# Mainboard_Geneva_Interface.net
KiCad netlist of a schematic drawn in Altium Designer
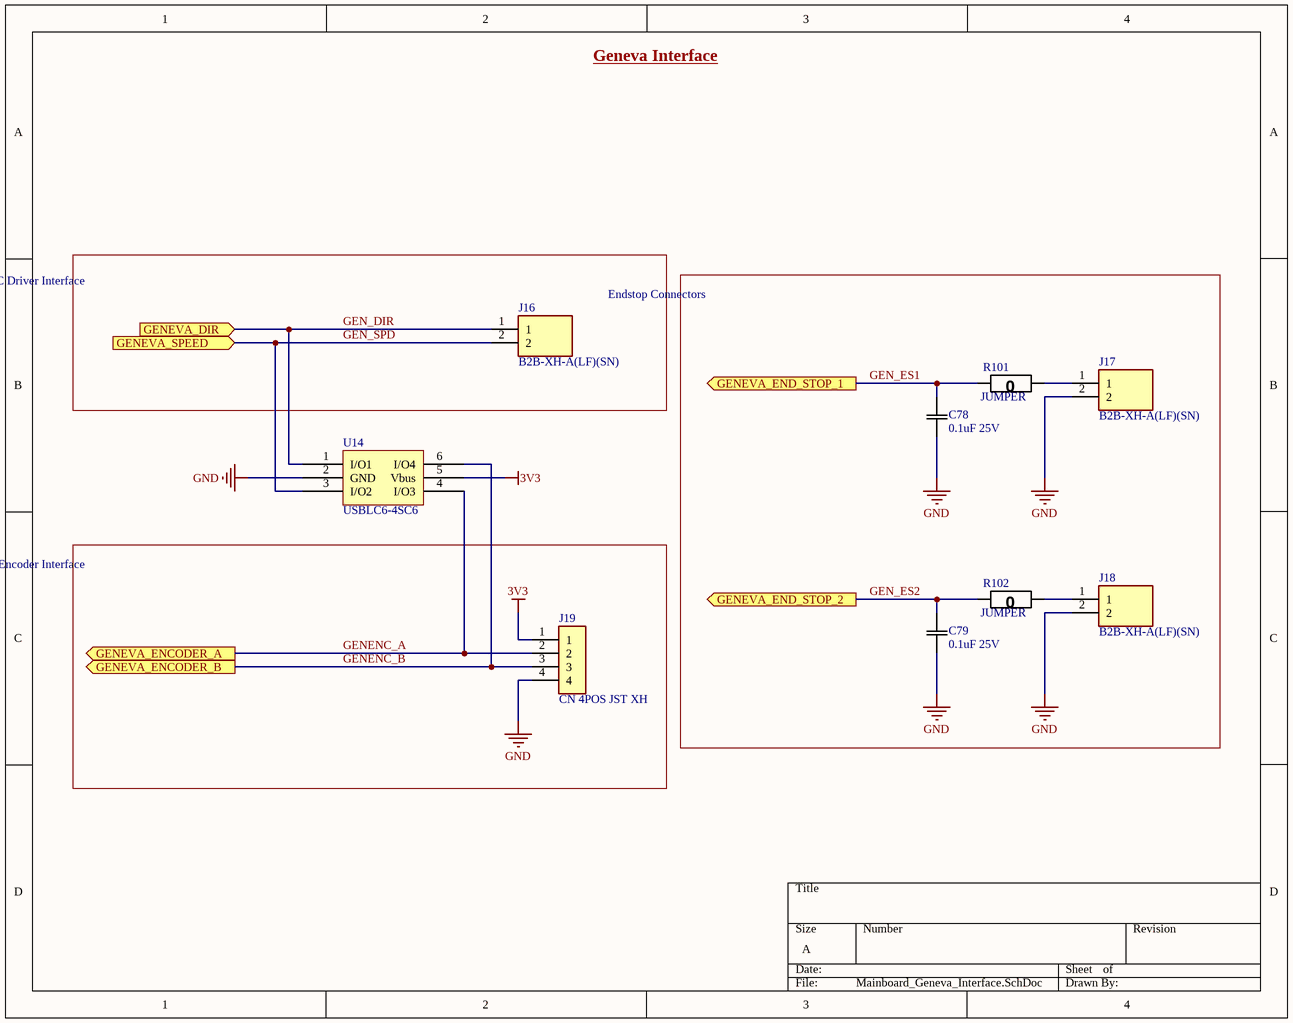
[diagram p0: Mainboard_Geneva_Interface.SchDoc]

(export (version "E")
  (design (tool "Eeschema 10.0.6"))
  (components
    (comp (ref "C78")
      (value "0.1uF 25V")
      (footprint "0805")
      (description "CAP CER 0.1UF 25V X7R 0805")
      (fields (field (name "TOLERANCE") "10%"))
      (libsource (lib "AltiumLibraries") (part "CAP 0.1uF 25V"))
    )
    (comp (ref "C79")
      (value "0.1uF 25V")
      (footprint "0805")
      (description "CAP CER 0.1UF 25V X7R 0805")
      (fields (field (name "TOLERANCE") "10%"))
      (libsource (lib "AltiumLibraries") (part "CAP 0.1uF 25V"))
    )
    (comp (ref "J16")
      (value "B2B-XH-A(LF)(SN)")
      (footprint "JST_B2B-XH-A(LF)(SN)")
      (description "Connector Header Through Hole 2 position 0.098 _2.50mm_\r\nJST XH")
      (fields (field (name "MP") "B2B-XH-A_LF__SN_") (field (name "MF") "JST Sales"))
      (libsource (lib "AltiumLibraries") (part "B2B-XH-A(LF)(SN)"))
    )
    (comp (ref "J17")
      (value "B2B-XH-A(LF)(SN)")
      (footprint "JST_B2B-XH-A(LF)(SN)")
      (description "Connector Header Through Hole 2 position 0.098 _2.50mm_\r\nJST XH")
      (fields (field (name "MP") "B2B-XH-A_LF__SN_") (field (name "MF") "JST Sales"))
      (libsource (lib "AltiumLibraries") (part "B2B-XH-A(LF)(SN)"))
    )
    (comp (ref "J18")
      (value "B2B-XH-A(LF)(SN)")
      (footprint "JST_B2B-XH-A(LF)(SN)")
      (description "Connector Header Through Hole 2 position 0.098 _2.50mm_\r\nJST XH")
      (fields (field (name "MP") "B2B-XH-A_LF__SN_") (field (name "MF") "JST Sales"))
      (libsource (lib "AltiumLibraries") (part "B2B-XH-A(LF)(SN)"))
    )
    (comp (ref "J19")
      (value "CN 4POS JST XH")
      (footprint "JST_B4B-XH-A(LF)(SN)")
      (description "Connector Header Through Hole 4 position 0.098 _2.50mm_\r\nB4B-XH-A(LF)(SN)")
      (fields (field (name "MP") "B4B-XH-A_LF__SN_") (field (name "MF") "JST Sales"))
      (libsource (lib "AltiumLibraries") (part "CN 4POS JST XH"))
    )
    (comp (ref "R101")
      (value "JUMPER")
      (footprint "0805")
      (description "RES SMD 0 OHM JUMPER GENERIC 0805")
      (libsource (lib "AltiumLibraries") (part "RES 0 JUMPER"))
    )
    (comp (ref "R102")
      (value "JUMPER")
      (footprint "0805")
      (description "RES SMD 0 OHM JUMPER GENERIC 0805")
      (libsource (lib "AltiumLibraries") (part "RES 0 JUMPER"))
    )
    (comp (ref "U14")
      (value "USBLC6-4SC6")
      (footprint "SOT23-6L")
      (libsource (lib "AltiumLibraries") (part "USBLC6-4SC6"))
    )
  )
  (nets
    (net (code "1") (name "/GENENC_A") (class "Default")
      (node (ref "J19") (pin "2") (pinfunction "2_2") (pintype "passive"))
      (node (ref "U14") (pin "4") (pinfunction "I/O3_4") (pintype "passive"))
    )
    (net (code "2") (name "/GENENC_B") (class "Default")
      (node (ref "J19") (pin "3") (pinfunction "3_3") (pintype "passive"))
      (node (ref "U14") (pin "6") (pinfunction "I/O4_6") (pintype "passive"))
    )
    (net (code "3") (name "/GEN_DIR") (class "Default")
      (node (ref "J16") (pin "1") (pinfunction "1_1") (pintype "passive"))
      (node (ref "U14") (pin "1") (pinfunction "I/O1_1") (pintype "passive"))
    )
    (net (code "4") (name "/GEN_ES1") (class "Default")
      (node (ref "C78") (pin "1") (pinfunction "C1_1") (pintype "passive"))
      (node (ref "R101") (pin "2") (pinfunction "R2_2") (pintype "passive"))
    )
    (net (code "5") (name "/GEN_ES2") (class "Default")
      (node (ref "C79") (pin "1") (pinfunction "C1_1") (pintype "passive"))
      (node (ref "R102") (pin "2") (pinfunction "R2_2") (pintype "passive"))
    )
    (net (code "6") (name "/GEN_SPD") (class "Default")
      (node (ref "J16") (pin "2") (pinfunction "2_2") (pintype "passive"))
      (node (ref "U14") (pin "3") (pinfunction "I/O2_3") (pintype "passive"))
    )
    (net (code "7") (name "3V3") (class "Default")
      (node (ref "J19") (pin "1") (pinfunction "1_1") (pintype "passive"))
      (node (ref "U14") (pin "5") (pinfunction "Vbus_5") (pintype "passive"))
    )
    (net (code "8") (name "GND") (class "Default")
      (node (ref "C78") (pin "2") (pinfunction "C2_2") (pintype "passive"))
      (node (ref "C79") (pin "2") (pinfunction "C2_2") (pintype "passive"))
      (node (ref "J17") (pin "2") (pinfunction "2_2") (pintype "passive"))
      (node (ref "J18") (pin "2") (pinfunction "2_2") (pintype "passive"))
      (node (ref "J19") (pin "4") (pinfunction "4_4") (pintype "passive"))
      (node (ref "U14") (pin "2") (pinfunction "GND_2") (pintype "passive"))
    )
    (net (code "9") (name "Net-(R101-R1)") (class "Default")
      (node (ref "J17") (pin "1") (pinfunction "1_1") (pintype "passive"))
      (node (ref "R101") (pin "1") (pinfunction "R1_1") (pintype "passive"))
    )
    (net (code "10") (name "Net-(R102-R1)") (class "Default")
      (node (ref "J18") (pin "1") (pinfunction "1_1") (pintype "passive"))
      (node (ref "R102") (pin "1") (pinfunction "R1_1") (pintype "passive"))
    )
  )
)
